# Zio_Qwiic_RGB_Color_Sensor_TCS34725.net
KiCad netlist of a schematic drawn in EAGLE
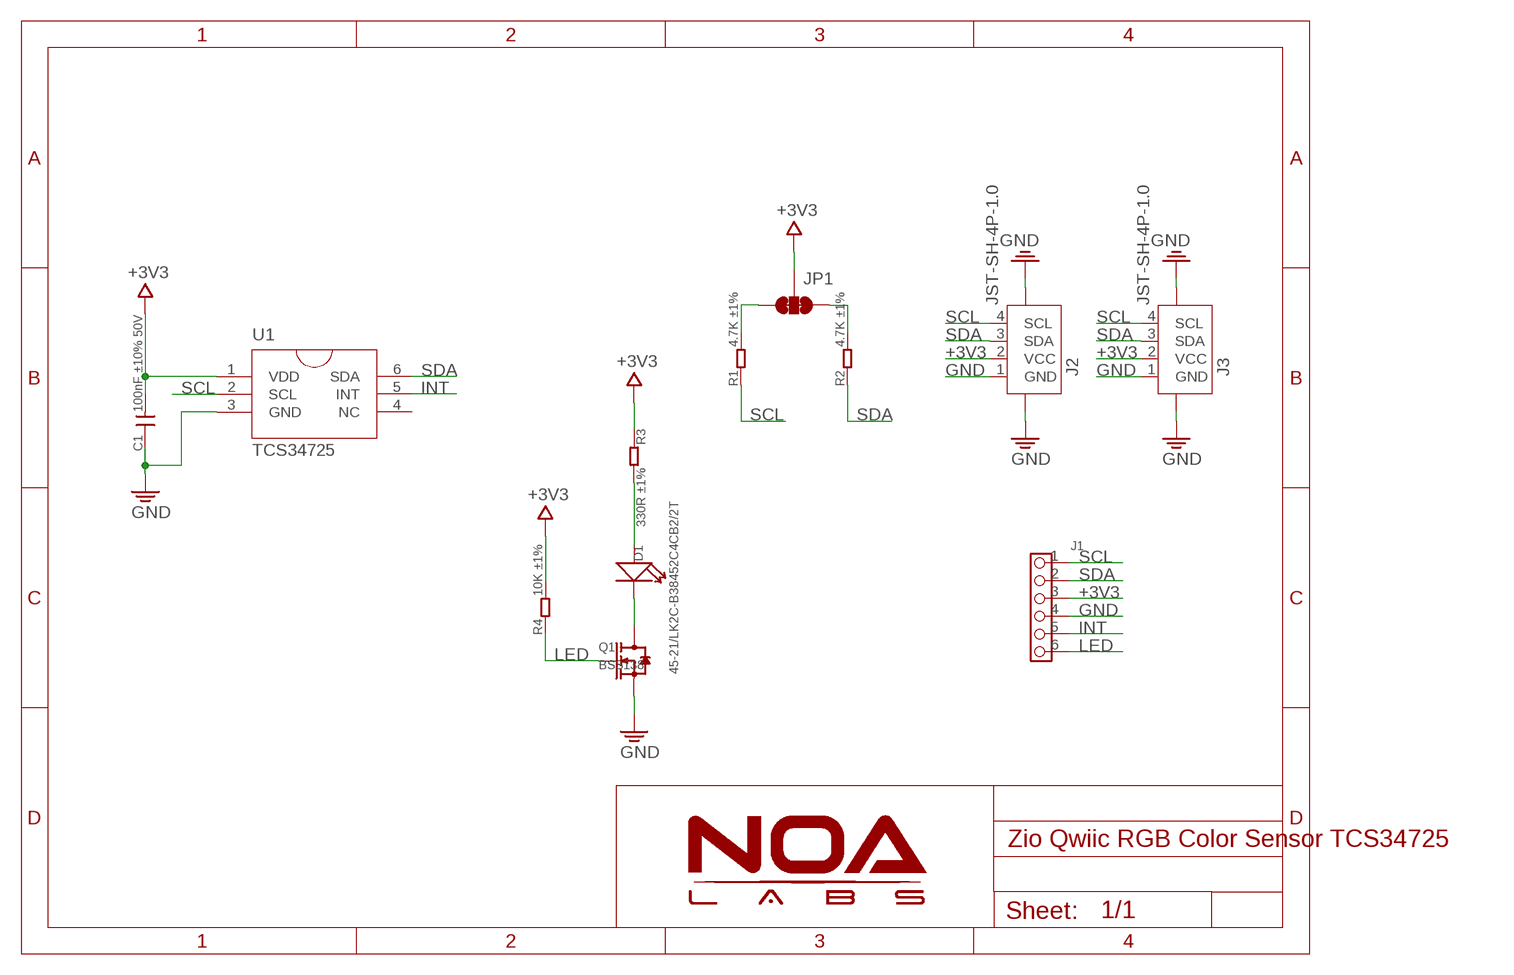
[diagram p0: schematic, sheet 1]

(export (version "E")
  (design (tool "Eeschema 10.0.6"))
  (components
    (comp (ref "C1")
      (value "100nF ±10% 50V")
      (footprint "eagle-import:C0603")
      (libsource (lib "eagle-import") (part "C-0603"))
    )
    (comp (ref "D1")
      (value "45-21/LK2C-B38452C4CB2/2T")
      (footprint "eagle-import:EVERLIGHT_45-21")
      (libsource (lib "eagle-import") (part "LED3020"))
    )
    (comp (ref "J1")
      (value "HEADER-6P-60/35MIL")
      (footprint "eagle-import:6P-2.54-60_35MIL")
      (libsource (lib "eagle-import") (part "HEADER-6P-60/35MIL"))
    )
    (comp (ref "J2")
      (value "JST-SH-4P-1.0")
      (footprint "eagle-import:JST-SH-4P")
      (libsource (lib "eagle-import") (part "JST-SH-4P-1.0"))
    )
    (comp (ref "J3")
      (value "JST-SH-4P-1.0")
      (footprint "eagle-import:JST-SH-4P")
      (libsource (lib "eagle-import") (part "JST-SH-4P-1.0"))
    )
    (comp (ref "JP1")
      (value "SMT-JUMPER_3_2-NC_TRACE")
      (footprint "eagle-import:SMT-JUMPER_3_2-NC_TRACE")
      (libsource (lib "eagle-import") (part "SMT-JUMPER_3_2-NC_TRACE"))
    )
    (comp (ref "Q1")
      (value "BSS138")
      (footprint "eagle-import:SOT23")
      (libsource (lib "eagle-import") (part "MOSFET-N-SOT23"))
    )
    (comp (ref "R1")
      (value "4.7K ±1%")
      (footprint "eagle-import:R0603")
      (libsource (lib "eagle-import") (part "R-0603"))
    )
    (comp (ref "R2")
      (value "4.7K ±1%")
      (footprint "eagle-import:R0603")
      (libsource (lib "eagle-import") (part "R-0603"))
    )
    (comp (ref "R3")
      (value "330R ±1%")
      (footprint "eagle-import:R0603")
      (libsource (lib "eagle-import") (part "R-0603"))
    )
    (comp (ref "R4")
      (value "10K ±1%")
      (footprint "eagle-import:R0603")
      (libsource (lib "eagle-import") (part "R-0603"))
    )
    (comp (ref "U1")
      (value "TCS34725")
      (footprint "eagle-import:FN6_TCS3472")
      (libsource (lib "eagle-import") (part "TCS34725"))
    )
  )
  (nets
    (net (code "1") (name "+3V3") (class "Default")
      (node (ref "C1") (pin "2") (pinfunction "2_2") (pintype "passive"))
      (node (ref "J1") (pin "3") (pinfunction "3_3") (pintype "bidirectional"))
      (node (ref "J2") (pin "2") (pinfunction "VCC_2") (pintype "bidirectional"))
      (node (ref "J3") (pin "2") (pinfunction "VCC_2") (pintype "bidirectional"))
      (node (ref "JP1") (pin "2") (pinfunction "2_2") (pintype "passive"))
      (node (ref "R3") (pin "1") (pinfunction "1_1") (pintype "passive"))
      (node (ref "R4") (pin "2") (pinfunction "2_2") (pintype "passive"))
      (node (ref "U1") (pin "1") (pinfunction "VDD_1") (pintype "bidirectional"))
    )
    (net (code "2") (name "/INT") (class "Default")
      (node (ref "J1") (pin "5") (pinfunction "5_5") (pintype "bidirectional"))
      (node (ref "U1") (pin "5") (pinfunction "INT_5") (pintype "bidirectional"))
    )
    (net (code "3") (name "/LED") (class "Default")
      (node (ref "J1") (pin "6") (pinfunction "6_6") (pintype "bidirectional"))
      (node (ref "Q1") (pin "1") (pinfunction "G_1") (pintype "passive"))
      (node (ref "R4") (pin "1") (pinfunction "1_1") (pintype "passive"))
    )
    (net (code "4") (name "/SCL") (class "Default")
      (node (ref "J1") (pin "1") (pinfunction "1_1") (pintype "bidirectional"))
      (node (ref "J2") (pin "4") (pinfunction "SCL_4") (pintype "bidirectional"))
      (node (ref "J3") (pin "4") (pinfunction "SCL_4") (pintype "bidirectional"))
      (node (ref "R1") (pin "1") (pinfunction "1_1") (pintype "passive"))
      (node (ref "U1") (pin "2") (pinfunction "SCL_2") (pintype "bidirectional"))
    )
    (net (code "5") (name "/SDA") (class "Default")
      (node (ref "J1") (pin "2") (pinfunction "2_2") (pintype "bidirectional"))
      (node (ref "J2") (pin "3") (pinfunction "SDA_3") (pintype "bidirectional"))
      (node (ref "J3") (pin "3") (pinfunction "SDA_3") (pintype "bidirectional"))
      (node (ref "R2") (pin "1") (pinfunction "1_1") (pintype "passive"))
      (node (ref "U1") (pin "6") (pinfunction "SDA_6") (pintype "bidirectional"))
    )
    (net (code "6") (name "GND") (class "Default")
      (node (ref "C1") (pin "1") (pinfunction "1_1") (pintype "passive"))
      (node (ref "J1") (pin "4") (pinfunction "4_4") (pintype "bidirectional"))
      (node (ref "J2") (pin "1") (pinfunction "GND_1") (pintype "bidirectional"))
      (node (ref "J2") (pin "NC1") (pinfunction "5_NC1") (pintype "bidirectional"))
      (node (ref "J2") (pin "NC2") (pinfunction "6_NC2") (pintype "bidirectional"))
      (node (ref "J3") (pin "1") (pinfunction "GND_1") (pintype "bidirectional"))
      (node (ref "J3") (pin "NC1") (pinfunction "5_NC1") (pintype "bidirectional"))
      (node (ref "J3") (pin "NC2") (pinfunction "6_NC2") (pintype "bidirectional"))
      (node (ref "Q1") (pin "2") (pinfunction "S_2") (pintype "passive"))
      (node (ref "U1") (pin "3") (pinfunction "GND_3") (pintype "bidirectional"))
    )
    (net (code "7") (name "Net-(D1-+)") (class "Default")
      (node (ref "D1") (pin "A") (pinfunction "+_A") (pintype "passive"))
      (node (ref "R3") (pin "2") (pinfunction "2_2") (pintype "passive"))
    )
    (net (code "8") (name "Net-(D1--)") (class "Default")
      (node (ref "D1") (pin "K") (pinfunction "-_K") (pintype "passive"))
      (node (ref "Q1") (pin "3") (pinfunction "D_3") (pintype "passive"))
    )
    (net (code "9") (name "Net-(JP1-Pad1)") (class "Default")
      (node (ref "JP1") (pin "1") (pinfunction "1_1") (pintype "passive"))
      (node (ref "R2") (pin "2") (pinfunction "2_2") (pintype "passive"))
    )
    (net (code "10") (name "Net-(JP1-Pad3)") (class "Default")
      (node (ref "JP1") (pin "3") (pinfunction "3_3") (pintype "passive"))
      (node (ref "R1") (pin "2") (pinfunction "2_2") (pintype "passive"))
    )
    (net (code "11") (name "unconnected-(U1-NC-Pad4)") (class "Default")
      (node (ref "U1") (pin "4") (pinfunction "NC_4") (pintype "bidirectional"))
    )
  )
)
